# DAC_channel.net
KiCad netlist of a schematic drawn in Altium Designer
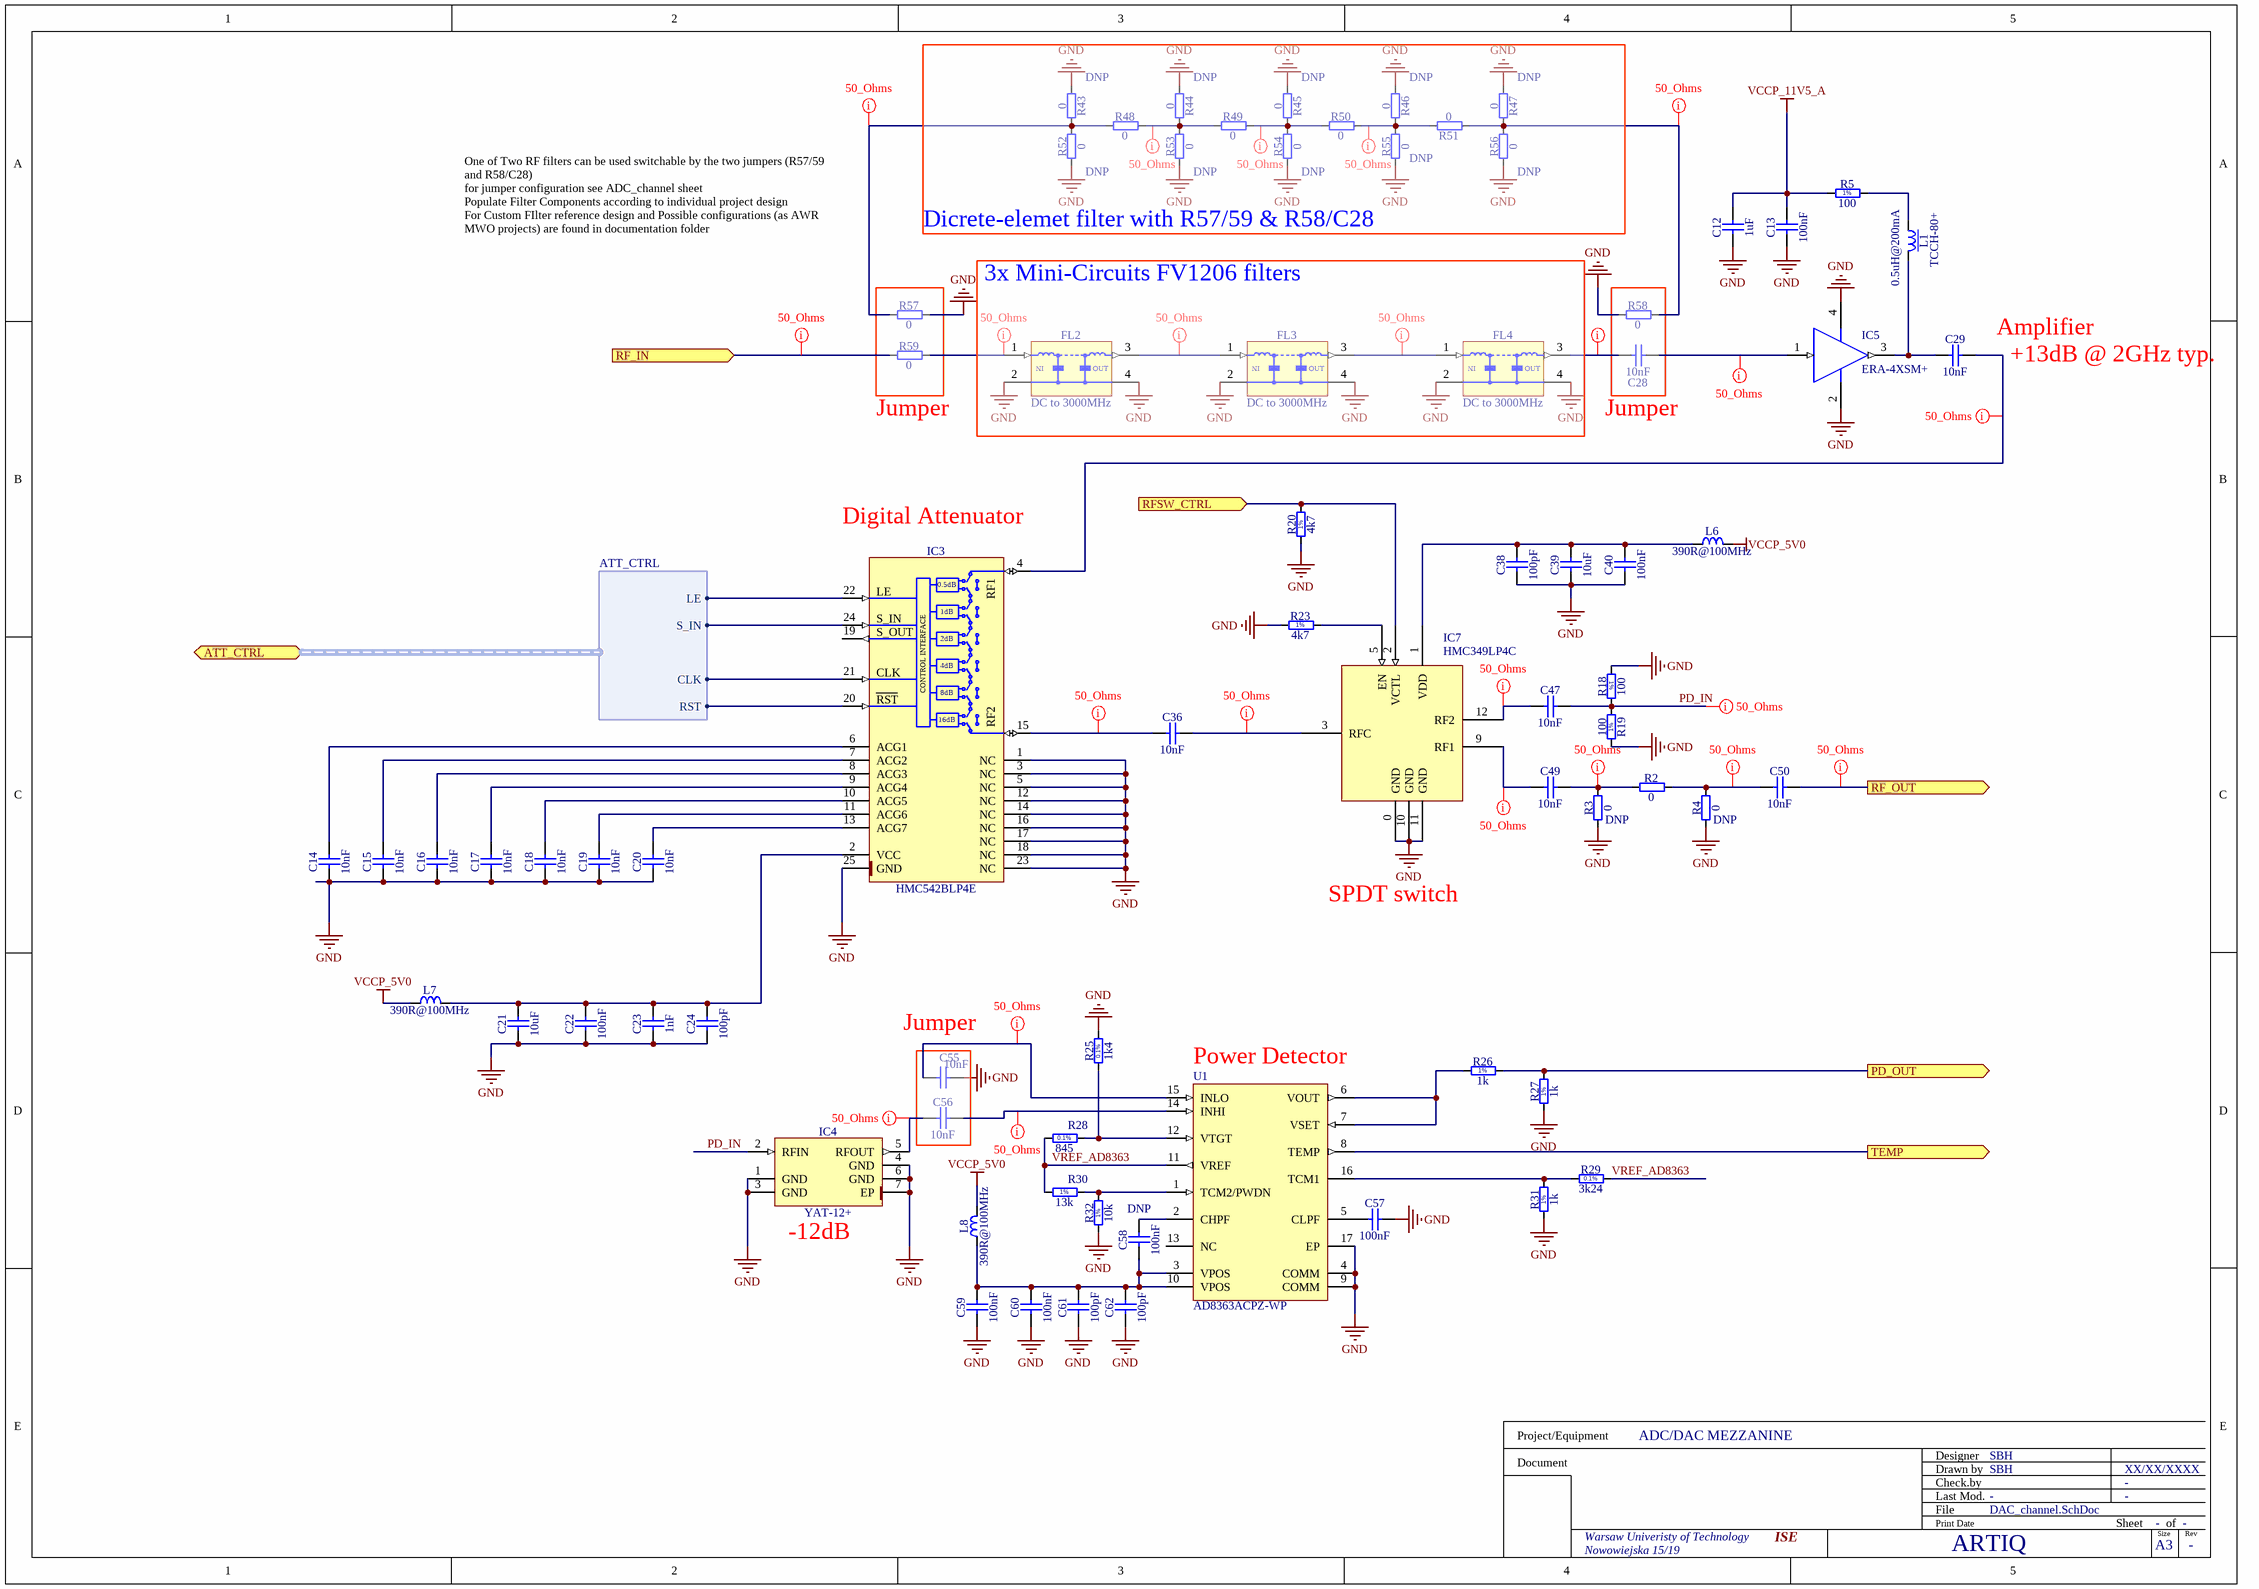
[diagram p0: DAC_channel.SchDoc]

(export (version "E")
  (design (tool "Eeschema 10.0.6"))
  (components
    (comp (ref "C12")
      (value "1uF")
      (footprint "CAPC2012X140N")
      (description "Non-polarised capacitor")
      (fields
        (field (name "PART NUMBER") "CC0805_1UF_35V_20%_X7R")
        (field (name "VOLTAGE") "35V")
        (field (name "AUTHOR") "CERN DEM JLC")
      )
      (libsource (lib "Capacitors") (part "Capacitor - non polarized"))
    )
    (comp (ref "C13")
      (value "100nF")
      (footprint "CAPC1608X87N")
      (description "Non-polarised capacitor")
      (fields
        (field (name "PART NUMBER") "CC0603_100NF_50V_10%_X7R")
        (field (name "VOLTAGE") "50V")
        (field (name "AUTHOR") "CERN DEM JLC")
      )
      (libsource (lib "Capacitors") (part "Capacitor - non polarized"))
    )
    (comp (ref "C14")
      (value "10nF")
      (footprint "CAPC1005X55N")
      (description "Non-polarised capacitor")
      (fields
        (field (name "PART NUMBER") "CC0402_10NF_16V_10%_X7R")
        (field (name "VOLTAGE") "16V")
        (field (name "AUTHOR") "CERN DEM JLC")
      )
      (libsource (lib "Capacitors") (part "Capacitor - non polarized"))
    )
    (comp (ref "C15")
      (value "10nF")
      (footprint "CAPC1005X55N")
      (description "Non-polarised capacitor")
      (fields
        (field (name "PART NUMBER") "CC0402_10NF_16V_10%_X7R")
        (field (name "VOLTAGE") "16V")
        (field (name "AUTHOR") "CERN DEM JLC")
      )
      (libsource (lib "Capacitors") (part "Capacitor - non polarized"))
    )
    (comp (ref "C16")
      (value "10nF")
      (footprint "CAPC1005X55N")
      (description "Non-polarised capacitor")
      (fields
        (field (name "PART NUMBER") "CC0402_10NF_16V_10%_X7R")
        (field (name "VOLTAGE") "16V")
        (field (name "AUTHOR") "CERN DEM JLC")
      )
      (libsource (lib "Capacitors") (part "Capacitor - non polarized"))
    )
    (comp (ref "C17")
      (value "10nF")
      (footprint "CAPC1005X55N")
      (description "Non-polarised capacitor")
      (fields
        (field (name "PART NUMBER") "CC0402_10NF_16V_10%_X7R")
        (field (name "VOLTAGE") "16V")
        (field (name "AUTHOR") "CERN DEM JLC")
      )
      (libsource (lib "Capacitors") (part "Capacitor - non polarized"))
    )
    (comp (ref "C18")
      (value "10nF")
      (footprint "CAPC1005X55N")
      (description "Non-polarised capacitor")
      (fields
        (field (name "PART NUMBER") "CC0402_10NF_16V_10%_X7R")
        (field (name "VOLTAGE") "16V")
        (field (name "AUTHOR") "CERN DEM JLC")
      )
      (libsource (lib "Capacitors") (part "Capacitor - non polarized"))
    )
    (comp (ref "C19")
      (value "10nF")
      (footprint "CAPC1005X55N")
      (description "Non-polarised capacitor")
      (fields
        (field (name "PART NUMBER") "CC0402_10NF_16V_10%_X7R")
        (field (name "VOLTAGE") "16V")
        (field (name "AUTHOR") "CERN DEM JLC")
      )
      (libsource (lib "Capacitors") (part "Capacitor - non polarized"))
    )
    (comp (ref "C20")
      (value "10nF")
      (footprint "CAPC1005X55N")
      (description "Non-polarised capacitor")
      (fields
        (field (name "PART NUMBER") "CC0402_10NF_16V_10%_X7R")
        (field (name "VOLTAGE") "16V")
        (field (name "AUTHOR") "CERN DEM JLC")
      )
      (libsource (lib "Capacitors") (part "Capacitor - non polarized"))
    )
    (comp (ref "C21")
      (value "10uF")
      (footprint "CAPC1608X80N")
      (description "Non-polarised capacitor")
      (fields
        (field (name "PART NUMBER") "CC0603_10UF_16V_20%_X5R")
        (field (name "VOLTAGE") "16V")
        (field (name "AUTHOR") "CERN DEM MR")
      )
      (libsource (lib "Capacitors") (part "Capacitor - non polarized"))
    )
    (comp (ref "C22")
      (value "100nF")
      (footprint "CAPC1005X55N")
      (description "Non-polarised capacitor")
      (fields
        (field (name "PART NUMBER") "CC0402_100NF_16V_10%_X7R")
        (field (name "VOLTAGE") "16V")
        (field (name "AUTHOR") "CERN DEM JLC")
      )
      (libsource (lib "Capacitors") (part "Capacitor - non polarized"))
    )
    (comp (ref "C23")
      (value "1nF")
      (footprint "CAPC1005X55N")
      (description "Non-polarised capacitor")
      (fields
        (field (name "PART NUMBER") "CC0402_1NF_50V_10%_X7R")
        (field (name "VOLTAGE") "50V")
        (field (name "AUTHOR") "CERN DEM JLC")
      )
      (libsource (lib "Capacitors") (part "Capacitor - non polarized"))
    )
    (comp (ref "C24")
      (value "100pF")
      (footprint "CAPC1005X55N")
      (description "Non-polarised capacitor")
      (fields
        (field (name "PART NUMBER") "CC0402_100PF_50V_5%_C0G")
        (field (name "VOLTAGE") "50V")
        (field (name "AUTHOR") "CERN DEM JLC")
      )
      (libsource (lib "Capacitors") (part "Capacitor - non polarized"))
    )
    (comp (ref "C28")
      (value "10nF")
      (footprint "CAPC1005X55N")
      (description "Non-polarised capacitor")
      (fields
        (field (name "PART NUMBER") "CC0402_10NF_16V_10%_X7R")
        (field (name "VOLTAGE") "16V")
        (field (name "AUTHOR") "CERN DEM JLC")
      )
      (libsource (lib "Capacitors") (part "Capacitor - non polarized"))
    )
    (comp (ref "C29")
      (value "10nF")
      (footprint "CAPC1005X55N")
      (description "Non-polarised capacitor")
      (fields
        (field (name "PART NUMBER") "CC0402_10NF_16V_10%_X7R")
        (field (name "VOLTAGE") "16V")
        (field (name "AUTHOR") "CERN DEM JLC")
      )
      (libsource (lib "Capacitors") (part "Capacitor - non polarized"))
    )
    (comp (ref "C36")
      (value "10nF")
      (footprint "CAPC1005X55N")
      (description "Non-polarised capacitor")
      (fields
        (field (name "PART NUMBER") "CC0402_10NF_16V_10%_X7R")
        (field (name "VOLTAGE") "16V")
        (field (name "AUTHOR") "CERN DEM JLC")
      )
      (libsource (lib "Capacitors") (part "Capacitor - non polarized"))
    )
    (comp (ref "C38")
      (value "100pF")
      (footprint "CAPC1005X55N")
      (description "Non-polarised capacitor")
      (fields
        (field (name "PART NUMBER") "CC0402_100PF_50V_5%_C0G")
        (field (name "VOLTAGE") "50V")
        (field (name "AUTHOR") "CERN DEM JLC")
      )
      (libsource (lib "Capacitors") (part "Capacitor - non polarized"))
    )
    (comp (ref "C39")
      (value "10uF")
      (footprint "CAPC1608X80N")
      (description "Non-polarised capacitor")
      (fields
        (field (name "PART NUMBER") "CC0603_10UF_16V_20%_X5R")
        (field (name "VOLTAGE") "16V")
        (field (name "AUTHOR") "CERN DEM MR")
      )
      (libsource (lib "Capacitors") (part "Capacitor - non polarized"))
    )
    (comp (ref "C40")
      (value "100nF")
      (footprint "CAPC1005X55N")
      (description "Non-polarised capacitor")
      (fields
        (field (name "PART NUMBER") "CC0402_100NF_16V_10%_X7R")
        (field (name "VOLTAGE") "16V")
        (field (name "AUTHOR") "CERN DEM JLC")
      )
      (libsource (lib "Capacitors") (part "Capacitor - non polarized"))
    )
    (comp (ref "C47")
      (value "10nF")
      (footprint "CAPC1005X55N")
      (description "Non-polarised capacitor")
      (fields
        (field (name "PART NUMBER") "CC0402_10NF_16V_10%_X7R")
        (field (name "VOLTAGE") "16V")
        (field (name "AUTHOR") "CERN DEM JLC")
      )
      (libsource (lib "Capacitors") (part "Capacitor - non polarized"))
    )
    (comp (ref "C49")
      (value "10nF")
      (footprint "CAPC1005X55N")
      (description "Non-polarised capacitor")
      (fields
        (field (name "PART NUMBER") "CC0402_10NF_16V_10%_X7R")
        (field (name "VOLTAGE") "16V")
        (field (name "AUTHOR") "CERN DEM JLC")
      )
      (libsource (lib "Capacitors") (part "Capacitor - non polarized"))
    )
    (comp (ref "C50")
      (value "10nF")
      (footprint "CAPC1005X55N")
      (description "Non-polarised capacitor")
      (fields
        (field (name "PART NUMBER") "CC0402_10NF_16V_10%_X7R")
        (field (name "VOLTAGE") "16V")
        (field (name "AUTHOR") "CERN DEM JLC")
      )
      (libsource (lib "Capacitors") (part "Capacitor - non polarized"))
    )
    (comp (ref "C55")
      (value "10nF")
      (footprint "CAPC1005X55N")
      (description "Non-polarised capacitor")
      (fields
        (field (name "PART NUMBER") "CC0402_10NF_16V_10%_X7R")
        (field (name "VOLTAGE") "16V")
        (field (name "AUTHOR") "CERN DEM JLC")
      )
      (libsource (lib "Capacitors") (part "Capacitor - non polarized"))
    )
    (comp (ref "C56")
      (value "10nF")
      (footprint "CAPC1005X55N")
      (description "Non-polarised capacitor")
      (fields
        (field (name "PART NUMBER") "CC0402_10NF_16V_10%_X7R")
        (field (name "VOLTAGE") "16V")
        (field (name "AUTHOR") "CERN DEM JLC")
      )
      (libsource (lib "Capacitors") (part "Capacitor - non polarized"))
    )
    (comp (ref "C57")
      (value "100nF")
      (footprint "CAPC1005X55N")
      (description "Non-polarised capacitor")
      (fields
        (field (name "PART NUMBER") "CC0402_100NF_16V_10%_X5R")
        (field (name "VOLTAGE") "16V")
        (field (name "AUTHOR") "CERN DEM JLC")
      )
      (libsource (lib "Capacitors") (part "Capacitor - non polarized"))
    )
    (comp (ref "C58")
      (value "100nF")
      (footprint "CAPC1005X55N")
      (description "Non-polarised capacitor")
      (fields
        (field (name "PART NUMBER") "CC0402_100NF_16V_10%_X5R")
        (field (name "VOLTAGE") "16V")
        (field (name "MOUNTED") "DNP")
        (field (name "AUTHOR") "CERN DEM JLC")
      )
      (libsource (lib "Capacitors") (part "Capacitor - non polarized"))
    )
    (comp (ref "C59")
      (value "100nF")
      (footprint "CAPC1005X55N")
      (description "Non-polarised capacitor")
      (fields
        (field (name "PART NUMBER") "CC0402_100NF_16V_10%_X5R")
        (field (name "VOLTAGE") "16V")
        (field (name "AUTHOR") "CERN DEM JLC")
      )
      (libsource (lib "Capacitors") (part "Capacitor - non polarized"))
    )
    (comp (ref "C60")
      (value "100nF")
      (footprint "CAPC1005X55N")
      (description "Non-polarised capacitor")
      (fields
        (field (name "PART NUMBER") "CC0402_100NF_16V_10%_X5R")
        (field (name "VOLTAGE") "16V")
        (field (name "AUTHOR") "CERN DEM JLC")
      )
      (libsource (lib "Capacitors") (part "Capacitor - non polarized"))
    )
    (comp (ref "C61")
      (value "100pF")
      (footprint "CAPC1005X55N")
      (description "Non-polarised capacitor")
      (fields
        (field (name "PART NUMBER") "CC0402_100PF_50V_5%_C0G")
        (field (name "VOLTAGE") "50V")
        (field (name "AUTHOR") "CERN DEM JLC")
      )
      (libsource (lib "Capacitors") (part "Capacitor - non polarized"))
    )
    (comp (ref "C62")
      (value "100pF")
      (footprint "CAPC1005X55N")
      (description "Non-polarised capacitor")
      (fields
        (field (name "PART NUMBER") "CC0402_100PF_50V_5%_C0G")
        (field (name "VOLTAGE") "50V")
        (field (name "AUTHOR") "CERN DEM JLC")
      )
      (libsource (lib "Capacitors") (part "Capacitor - non polarized"))
    )
    (comp (ref "FL2")
      (value "DC to 3000MHz")
      (footprint "FIL_MINI-CIRCUITS_FV1206")
      (description "50 Ohm DC to 3000MHz Low Pass Filter")
      (fields
        (field (name "PART NUMBER") "FIL_MINI-CIRCUITS_LFCN-3000+")
        (field (name "MANUFACTURER") "MINI-CIRCUITS")
        (field (name "AUTHOR") "CERN DEM JLC")
      )
      (libsource (lib "Inductors & Transformers") (part "FIL_MINI-CIRCUITS_LFCN-3000+"))
    )
    (comp (ref "FL3")
      (value "DC to 3000MHz")
      (footprint "FIL_MINI-CIRCUITS_FV1206")
      (description "50 Ohm DC to 3000MHz Low Pass Filter")
      (fields
        (field (name "PART NUMBER") "FIL_MINI-CIRCUITS_LFCN-3000+")
        (field (name "MANUFACTURER") "MINI-CIRCUITS")
        (field (name "AUTHOR") "CERN DEM JLC")
      )
      (libsource (lib "Inductors & Transformers") (part "FIL_MINI-CIRCUITS_LFCN-3000+"))
    )
    (comp (ref "FL4")
      (value "DC to 3000MHz")
      (footprint "FIL_MINI-CIRCUITS_FV1206")
      (description "50 Ohm DC to 3000MHz Low Pass Filter")
      (fields
        (field (name "PART NUMBER") "FIL_MINI-CIRCUITS_LFCN-3000+")
        (field (name "MANUFACTURER") "MINI-CIRCUITS")
        (field (name "AUTHOR") "CERN DEM JLC")
      )
      (libsource (lib "Inductors & Transformers") (part "FIL_MINI-CIRCUITS_LFCN-3000+"))
    )
    (comp (ref "IC3")
      (value "HMC542BLP4E")
      (footprint "QFN50P400X400X100-25N-S295")
      (description "0.5dB LSB GaAs MMIC 6-bit Digital Serial Control Attenuator, DC - 4GHz")
      (fields (field (name "MANUFACTURER") "HITTITE MICROWAVE CORP") (field (name "AUTHOR") "CERN DEM JMW"))
      (libsource (lib "ICs And Semiconductors") (part "HMC542BLP4E"))
    )
    (comp (ref "IC4")
      (value "YAT-12+")
      (footprint "MINI-CIRCUITS_MC1630")
      (description "DC to 18GHz, 2W, 50 Ohm, 4dB Attenuator")
      (fields (field (name "MANUFACTURER") "MINI-CIRCUITS") (field (name "AUTHOR") "CERN DEM JLC"))
      (libsource (lib "ICs And Semiconductors") (part "YAT-XX+"))
    )
    (comp (ref "IC5")
      (value "ERA-4XSM+")
      (footprint "MINI-CIRCUITS_WW107")
      (description "DC-4GHz Monolithic Amplifier")
      (fields (field (name "MANUFACTURER") "MINI-CIRCUITS") (field (name "AUTHOR") "CERN DEM JMW"))
      (libsource (lib "ICs And Semiconductors") (part "ERA-4XSM+"))
    )
    (comp (ref "IC7")
      (value "HMC349LP4C")
      (footprint "uRFB_CLKIN3:QFN65P400X400X100-16N")
      (description "Hittite RF Switch, SPDT, Non-Reflective")
      (libsource (lib "uRFB_CLKIN3") (part "HMC349LP4C"))
    )
    (comp (ref "L1")
      (value "0.5uH@200mA")
      (footprint "IND_MINI-CIRCUITS_GU1604")
      (description "50 Ohms, 50 to 8200 MHz RF Choke")
      (fields
        (field (name "PART NUMBER") "IND_MINI-CIRCUITS_TCCH-80+")
        (field (name "POWER") "200mA")
        (field (name "MANUFACTURER PART NUMBER") "TCCH-80+")
        (field (name "AUTHOR") "CERN DEM JLC")
      )
      (libsource (lib "Inductors & Transformers") (part "IND_MINI-CIRCUITS_TCCH-80+"))
    )
    (comp (ref "L6")
      (value "390R@100MHz")
      (footprint "INDC1608X95N")
      (description "Inductor")
      (fields
        (field (name "PART NUMBER") "IND0603_TDK_MPZ1608R391A")
        (field (name "POWER") "1.2A")
        (field (name "AUTHOR") "CERN DEM JLC")
      )
      (libsource (lib "Inductors & Transformers") (part "Inductor"))
    )
    (comp (ref "L7")
      (value "390R@100MHz")
      (footprint "INDC1608X95N")
      (description "Inductor")
      (fields
        (field (name "PART NUMBER") "IND0603_TDK_MPZ1608R391A")
        (field (name "POWER") "1.2A")
        (field (name "AUTHOR") "CERN DEM JLC")
      )
      (libsource (lib "Inductors & Transformers") (part "Inductor"))
    )
    (comp (ref "L8")
      (value "390R@100MHz")
      (footprint "INDC1608X95N")
      (description "Inductor")
      (fields
        (field (name "PART NUMBER") "IND0603_TDK_MPZ1608R391A")
        (field (name "POWER") "1.2A")
        (field (name "AUTHOR") "CERN DEM JLC")
      )
      (libsource (lib "") (part "Inductor_1"))
    )
    (comp (ref "R2")
      (value "0")
      (footprint "RESC1005X40N")
      (description "Resistor")
      (fields
        (field (name "PART NUMBER") "R0402_0R_JUMPER")
        (field (name "MANUFACTURER") "GENERIC")
        (field (name "AUTHOR") "CERN DEM JLC")
      )
      (libsource (lib "Resistors") (part "Resistor"))
    )
    (comp (ref "R3")
      (value "0")
      (footprint "RESC1005X40N")
      (description "Resistor")
      (fields
        (field (name "PART NUMBER") "R0402_0R_JUMPER")
        (field (name "MANUFACTURER") "GENERIC")
        (field (name "MOUNTED") "DNP")
        (field (name "AUTHOR") "CERN DEM JLC")
      )
      (libsource (lib "Resistors") (part "Resistor"))
    )
    (comp (ref "R4")
      (value "0")
      (footprint "RESC1005X40N")
      (description "Resistor")
      (fields
        (field (name "PART NUMBER") "R0402_0R_JUMPER")
        (field (name "MANUFACTURER") "GENERIC")
        (field (name "MOUNTED") "DNP")
        (field (name "AUTHOR") "CERN DEM JLC")
      )
      (libsource (lib "Resistors") (part "Resistor"))
    )
    (comp (ref "R5")
      (value "100")
      (footprint "RESC3216X65N")
      (description "Resistor - 1%")
      (fields
        (field (name "PART NUMBER") "R1206_100R_1%_0.25W_100PPM")
        (field (name "POWER") "0.25W")
        (field (name "AUTHOR") "CERN DEM JLC")
      )
      (libsource (lib "Resistors") (part "Resistor - 1%"))
    )
    (comp (ref "R18")
      (value "100")
      (footprint "RESC0603X28N")
      (description "Resistor - 1%")
      (fields
        (field (name "PART NUMBER") "R0201_100R_1%_0.05W_200PPM")
        (field (name "POWER") "0.05W")
        (field (name "AUTHOR") "CERN DEM JLC")
      )
      (libsource (lib "Resistors") (part "Resistor - 1%"))
    )
    (comp (ref "R19")
      (value "100")
      (footprint "RESC0603X28N")
      (description "Resistor - 1%")
      (fields
        (field (name "PART NUMBER") "R0201_100R_1%_0.05W_200PPM")
        (field (name "POWER") "0.05W")
        (field (name "AUTHOR") "CERN DEM JLC")
      )
      (libsource (lib "Resistors") (part "Resistor - 1%"))
    )
    (comp (ref "R20")
      (value "4k7")
      (footprint "RESC1005X40N")
      (description "Resistor - 1%")
      (fields
        (field (name "PART NUMBER") "R0402_4K7_1%_0.0625W_100PPM")
        (field (name "POWER") "0.0625W")
        (field (name "AUTHOR") "CERN DEM JLC")
      )
      (libsource (lib "Resistors") (part "Resistor - 1%"))
    )
    (comp (ref "R23")
      (value "4k7")
      (footprint "RESC1005X40N")
      (description "Resistor - 1%")
      (fields
        (field (name "PART NUMBER") "R0402_4K7_1%_0.0625W_100PPM")
        (field (name "POWER") "0.0625W")
        (field (name "AUTHOR") "CERN DEM JLC")
      )
      (libsource (lib "Resistors") (part "Resistor - 1%"))
    )
    (comp (ref "R25")
      (value "1k4")
      (footprint "RESC1608X55N")
      (description "Resistor - 0.1%")
      (fields
        (field (name "PART NUMBER") "R0603_1K4_0.1%_0.063W_10PPM")
        (field (name "POWER") "0.063W")
        (field (name "AUTHOR") "CERN DEM JLC")
      )
      (libsource (lib "Resistors") (part "Resistor - 0.1%"))
    )
    (comp (ref "R26")
      (value "1k")
      (footprint "RESC1005X40N")
      (description "Resistor - 1%")
      (fields
        (field (name "PART NUMBER") "R0402_1K_1%_0.0625W_100PPM")
        (field (name "POWER") "0.0625W")
        (field (name "AUTHOR") "CERN DEM JLC")
      )
      (libsource (lib "Resistors") (part "Resistor - 1%"))
    )
    (comp (ref "R27")
      (value "1k")
      (footprint "RESC1005X40N")
      (description "Resistor - 1%")
      (fields
        (field (name "PART NUMBER") "R0402_1K_1%_0.0625W_100PPM")
        (field (name "POWER") "0.0625W")
        (field (name "AUTHOR") "CERN DEM JLC")
      )
      (libsource (lib "Resistors") (part "Resistor - 1%"))
    )
    (comp (ref "R28")
      (value "845")
      (footprint "RESC1608X55N")
      (description "Resistor - 0.1%")
      (fields
        (field (name "PART NUMBER") "R0603_845R_0.1%_0.063W_10PPM")
        (field (name "POWER") "0.063W")
        (field (name "AUTHOR") "CERN DEM JLC")
      )
      (libsource (lib "Resistors") (part "Resistor - 0.1%"))
    )
    (comp (ref "R29")
      (value "3k24")
      (footprint "RESC1608X55N")
      (description "Resistor - 0.1%")
      (fields
        (field (name "PART NUMBER") "R0603_3K24_0.1%_0.063W_10PPM")
        (field (name "POWER") "0.063W")
        (field (name "AUTHOR") "CERN DEM JLC")
      )
      (libsource (lib "Resistors") (part "Resistor - 0.1%"))
    )
    (comp (ref "R30")
      (value "13k")
      (footprint "RESC1005X40N")
      (description "Resistor - 1%")
      (fields
        (field (name "PART NUMBER") "R0402_13K_1%_0.0625W_100PPM")
        (field (name "POWER") "0.0625W")
        (field (name "AUTHOR") "CERN DEM JLC")
      )
      (libsource (lib "Resistors") (part "Resistor - 1%"))
    )
    (comp (ref "R31")
      (value "1k")
      (footprint "RESC1005X40N")
      (description "Resistor - 1%")
      (fields
        (field (name "PART NUMBER") "R0402_1K_1%_0.0625W_100PPM")
        (field (name "POWER") "0.0625W")
        (field (name "AUTHOR") "CERN DEM JLC")
      )
      (libsource (lib "Resistors") (part "Resistor - 1%"))
    )
    (comp (ref "R32")
      (value "10k")
      (footprint "RESC1005X40N")
      (description "Resistor - 1%")
      (fields
        (field (name "PART NUMBER") "R0402_10K_1%_0.0625W_100PPM")
        (field (name "POWER") "0.0625W")
        (field (name "AUTHOR") "CERN DEM JLC")
      )
      (libsource (lib "Resistors") (part "Resistor - 1%"))
    )
    (comp (ref "R43")
      (value "0")
      (footprint "RESC1005X40N")
      (description "Resistor")
      (fields
        (field (name "PART NUMBER") "R0402_0R_JUMPER")
        (field (name "MANUFACTURER") "GENERIC")
        (field (name "MOUNTED") "DNP")
        (field (name "AUTHOR") "CERN DEM JLC")
      )
      (libsource (lib "Resistors") (part "Resistor"))
    )
    (comp (ref "R44")
      (value "0")
      (footprint "RESC1005X40N")
      (description "Resistor")
      (fields
        (field (name "PART NUMBER") "R0402_0R_JUMPER")
        (field (name "MANUFACTURER") "GENERIC")
        (field (name "MOUNTED") "DNP")
        (field (name "AUTHOR") "CERN DEM JLC")
      )
      (libsource (lib "Resistors") (part "Resistor"))
    )
    (comp (ref "R45")
      (value "0")
      (footprint "RESC1005X40N")
      (description "Resistor")
      (fields
        (field (name "PART NUMBER") "R0402_0R_JUMPER")
        (field (name "MANUFACTURER") "GENERIC")
        (field (name "MOUNTED") "DNP")
        (field (name "AUTHOR") "CERN DEM JLC")
      )
      (libsource (lib "Resistors") (part "Resistor"))
    )
    (comp (ref "R46")
      (value "0")
      (footprint "RESC1005X40N")
      (description "Resistor")
      (fields
        (field (name "PART NUMBER") "R0402_0R_JUMPER")
        (field (name "MANUFACTURER") "GENERIC")
        (field (name "MOUNTED") "DNP")
        (field (name "AUTHOR") "CERN DEM JLC")
      )
      (libsource (lib "Resistors") (part "Resistor"))
    )
    (comp (ref "R47")
      (value "0")
      (footprint "RESC1005X40N")
      (description "Resistor")
      (fields
        (field (name "PART NUMBER") "R0402_0R_JUMPER")
        (field (name "MANUFACTURER") "GENERIC")
        (field (name "MOUNTED") "DNP")
        (field (name "AUTHOR") "CERN DEM JLC")
      )
      (libsource (lib "Resistors") (part "Resistor"))
    )
    (comp (ref "R48")
      (value "0")
      (footprint "RESC1005X40N")
      (description "Resistor")
      (fields
        (field (name "PART NUMBER") "R0402_0R_JUMPER")
        (field (name "MANUFACTURER") "GENERIC")
        (field (name "AUTHOR") "CERN DEM JLC")
      )
      (libsource (lib "Resistors") (part "Resistor"))
    )
    (comp (ref "R49")
      (value "0")
      (footprint "RESC1005X40N")
      (description "Resistor")
      (fields
        (field (name "PART NUMBER") "R0402_0R_JUMPER")
        (field (name "MANUFACTURER") "GENERIC")
        (field (name "AUTHOR") "CERN DEM JLC")
      )
      (libsource (lib "Resistors") (part "Resistor"))
    )
    (comp (ref "R50")
      (value "0")
      (footprint "RESC1005X40N")
      (description "Resistor")
      (fields
        (field (name "PART NUMBER") "R0402_0R_JUMPER")
        (field (name "MANUFACTURER") "GENERIC")
        (field (name "AUTHOR") "CERN DEM JLC")
      )
      (libsource (lib "Resistors") (part "Resistor"))
    )
    (comp (ref "R51")
      (value "0")
      (footprint "RESC1005X40N")
      (description "Resistor")
      (fields
        (field (name "PART NUMBER") "R0402_0R_JUMPER")
        (field (name "MANUFACTURER") "GENERIC")
        (field (name "AUTHOR") "CERN DEM JLC")
      )
      (libsource (lib "Resistors") (part "Resistor"))
    )
    (comp (ref "R52")
      (value "0")
      (footprint "RESC1005X40N")
      (description "Resistor")
      (fields
        (field (name "PART NUMBER") "R0402_0R_JUMPER")
        (field (name "MANUFACTURER") "GENERIC")
        (field (name "MOUNTED") "DNP")
        (field (name "AUTHOR") "CERN DEM JLC")
      )
      (libsource (lib "Resistors") (part "Resistor"))
    )
    (comp (ref "R53")
      (value "0")
      (footprint "RESC1005X40N")
      (description "Resistor")
      (fields
        (field (name "PART NUMBER") "R0402_0R_JUMPER")
        (field (name "MANUFACTURER") "GENERIC")
        (field (name "MOUNTED") "DNP")
        (field (name "AUTHOR") "CERN DEM JLC")
      )
      (libsource (lib "Resistors") (part "Resistor"))
    )
    (comp (ref "R54")
      (value "0")
      (footprint "RESC1005X40N")
      (description "Resistor")
      (fields
        (field (name "PART NUMBER") "R0402_0R_JUMPER")
        (field (name "MANUFACTURER") "GENERIC")
        (field (name "MOUNTED") "DNP")
        (field (name "AUTHOR") "CERN DEM JLC")
      )
      (libsource (lib "Resistors") (part "Resistor"))
    )
    (comp (ref "R55")
      (value "0")
      (footprint "RESC1005X40N")
      (description "Resistor")
      (fields
        (field (name "PART NUMBER") "R0402_0R_JUMPER")
        (field (name "MANUFACTURER") "GENERIC")
        (field (name "MOUNTED") "DNP")
        (field (name "AUTHOR") "CERN DEM JLC")
      )
      (libsource (lib "Resistors") (part "Resistor"))
    )
    (comp (ref "R56")
      (value "0")
      (footprint "RESC1005X40N")
      (description "Resistor")
      (fields
        (field (name "PART NUMBER") "R0402_0R_JUMPER")
        (field (name "MANUFACTURER") "GENERIC")
        (field (name "MOUNTED") "DNP")
        (field (name "AUTHOR") "CERN DEM JLC")
      )
      (libsource (lib "Resistors") (part "Resistor"))
    )
    (comp (ref "R57")
      (value "0")
      (footprint "RESC1005X40N")
      (description "Resistor")
      (fields
        (field (name "PART NUMBER") "R0402_0R_JUMPER")
        (field (name "MANUFACTURER") "GENERIC")
        (field (name "AUTHOR") "CERN DEM JLC")
      )
      (libsource (lib "Resistors") (part "Resistor"))
    )
    (comp (ref "R58")
      (value "0")
      (footprint "RESC1005X40N")
      (description "Resistor")
      (fields
        (field (name "PART NUMBER") "R0402_0R_JUMPER")
        (field (name "MANUFACTURER") "GENERIC")
        (field (name "AUTHOR") "CERN DEM JLC")
      )
      (libsource (lib "Resistors") (part "Resistor"))
    )
    (comp (ref "R59")
      (value "0")
      (footprint "RESC1005X40N")
      (description "Resistor")
      (fields
        (field (name "PART NUMBER") "R0402_0R_JUMPER")
        (field (name "MANUFACTURER") "GENERIC")
        (field (name "AUTHOR") "CERN DEM JLC")
      )
      (libsource (lib "Resistors") (part "Resistor"))
    )
    (comp (ref "U1")
      (value "AD8363ACPZ-WP")
      (footprint "ADI-CP-16-10_M")
      (description "50 Hz to 6 GHz,50 dB TruPwr™ Detector, 3µs Response Time, CP-16-10, Pb-Free, 64 Tray")
      (libsource (lib "Altium Content Vault") (part "ADI-AD8363-CP-16-10"))
    )
  )
  (nets
    (net (code "2") (name "/CLK") (class "Default")
      (node (ref "IC3") (pin "21") (pinfunction "SHIFT_CLOCK_21") (pintype "input"))
    )
    (net (code "3") (name "/LE") (class "Default")
      (node (ref "IC3") (pin "22") (pinfunction "LATCH_ENABLE_22") (pintype "input"))
    )
    (net (code "4") (name "/PD_IN") (class "Default")
      (node (ref "C47") (pin "2") (pinfunction "2_2") (pintype "passive"))
      (node (ref "IC4") (pin "2") (pinfunction "RFIN_2") (pintype "input"))
      (node (ref "R18") (pin "2") (pinfunction "2_2") (pintype "passive"))
      (node (ref "R19") (pin "2") (pinfunction "2_2") (pintype "passive"))
    )
    (net (code "5") (name "/PD_OUT") (class "Default")
      (node (ref "R26") (pin "2") (pinfunction "2_2") (pintype "passive"))
      (node (ref "R27") (pin "2") (pinfunction "2_2") (pintype "passive"))
    )
    (net (code "6") (name "/RFSW_CTRL") (class "Default")
      (node (ref "IC7") (pin "2") (pinfunction "VCTL_2") (pintype "input"))
      (node (ref "R20") (pin "2") (pinfunction "2_2") (pintype "passive"))
    )
    (net (code "7") (name "/RF_IN") (class "Default")
      (node (ref "R59") (pin "1") (pinfunction "1_1") (pintype "passive"))
    )
    (net (code "8") (name "/RF_OUT") (class "Default")
      (node (ref "C50") (pin "2") (pinfunction "2_2") (pintype "passive"))
    )
    (net (code "9") (name "/RST") (class "Default")
      (node (ref "IC3") (pin "20") (pinfunction "~{RESET}_20") (pintype "input"))
    )
    (net (code "10") (name "/S_IN") (class "Default")
      (node (ref "IC3") (pin "24") (pinfunction "SERIAL_INPUT_24") (pintype "input"))
    )
    (net (code "11") (name "/TEMP") (class "Default")
      (node (ref "U1") (pin "8") (pinfunction "TEMP_8") (pintype "output"))
    )
    (net (code "12") (name "/VREF_AD8363") (class "Default")
      (node (ref "R28") (pin "1") (pinfunction "1_1") (pintype "passive"))
      (node (ref "R29") (pin "2") (pinfunction "2_2") (pintype "passive"))
      (node (ref "R30") (pin "1") (pinfunction "1_1") (pintype "passive"))
      (node (ref "U1") (pin "11") (pinfunction "VREF_11") (pintype "output"))
    )
    (net (code "14") (name "GND") (class "Default")
      (node (ref "C12") (pin "1") (pinfunction "1_1") (pintype "passive"))
      (node (ref "C13") (pin "1") (pinfunction "1_1") (pintype "passive"))
      (node (ref "C14") (pin "1") (pinfunction "1_1") (pintype "passive"))
      (node (ref "C15") (pin "1") (pinfunction "1_1") (pintype "passive"))
      (node (ref "C16") (pin "1") (pinfunction "1_1") (pintype "passive"))
      (node (ref "C17") (pin "1") (pinfunction "1_1") (pintype "passive"))
      (node (ref "C18") (pin "1") (pinfunction "1_1") (pintype "passive"))
      (node (ref "C19") (pin "1") (pinfunction "1_1") (pintype "passive"))
      (node (ref "C20") (pin "1") (pinfunction "1_1") (pintype "passive"))
      (node (ref "C21") (pin "1") (pinfunction "1_1") (pintype "passive"))
      (node (ref "C22") (pin "1") (pinfunction "1_1") (pintype "passive"))
      (node (ref "C23") (pin "1") (pinfunction "1_1") (pintype "passive"))
      (node (ref "C24") (pin "1") (pinfunction "1_1") (pintype "passive"))
      (node (ref "C38") (pin "2") (pinfunction "2_2") (pintype "passive"))
      (node (ref "C39") (pin "1") (pinfunction "1_1") (pintype "passive"))
      (node (ref "C40") (pin "1") (pinfunction "1_1") (pintype "passive"))
      (node (ref "C55") (pin "1") (pinfunction "1_1") (pintype "passive"))
      (node (ref "C57") (pin "2") (pinfunction "2_2") (pintype "passive"))
      (node (ref "C59") (pin "1") (pinfunction "1_1") (pintype "passive"))
      (node (ref "C60") (pin "1") (pinfunction "1_1") (pintype "passive"))
      (node (ref "C61") (pin "2") (pinfunction "2_2") (pintype "passive"))
      (node (ref "C62") (pin "2") (pinfunction "2_2") (pintype "passive"))
      (node (ref "FL2") (pin "2") (pinfunction "GND_2") (pintype "power_in"))
      (node (ref "FL2") (pin "4") (pinfunction "GND_4") (pintype "power_in"))
      (node (ref "FL3") (pin "2") (pinfunction "GND_2") (pintype "power_in"))
      (node (ref "FL3") (pin "4") (pinfunction "GND_4") (pintype "power_in"))
      (node (ref "FL4") (pin "2") (pinfunction "GND_2") (pintype "power_in"))
      (node (ref "FL4") (pin "4") (pinfunction "GND_4") (pintype "power_in"))
      (node (ref "IC3") (pin "1") (pinfunction "NC_1") (pintype "passive"))
      (node (ref "IC3") (pin "12") (pinfunction "NC_12") (pintype "passive"))
      (node (ref "IC3") (pin "14") (pinfunction "NC_14") (pintype "passive"))
      (node (ref "IC3") (pin "16") (pinfunction "NC_16") (pintype "passive"))
      (node (ref "IC3") (pin "17") (pinfunction "NC_17") (pintype "passive"))
      (node (ref "IC3") (pin "18") (pinfunction "NC_18") (pintype "passive"))
      (node (ref "IC3") (pin "23") (pinfunction "NC_23") (pintype "passive"))
      (node (ref "IC3") (pin "25") (pinfunction "GND_25") (pintype "power_in"))
      (node (ref "IC3") (pin "3") (pinfunction "NC_3") (pintype "passive"))
      (node (ref "IC3") (pin "5") (pinfunction "NC_5") (pintype "passive"))
      (node (ref "IC4") (pin "1") (pinfunction "GND_1") (pintype "power_in"))
      (node (ref "IC4") (pin "3") (pinfunction "GND_3") (pintype "power_in"))
      (node (ref "IC4") (pin "4") (pinfunction "GND_4") (pintype "power_in"))
      (node (ref "IC4") (pin "6") (pinfunction "GND_6") (pintype "power_in"))
      (node (ref "IC4") (pin "7") (pinfunction "EP_7") (pintype "power_in"))
      (node (ref "IC5") (pin "2") (pinfunction "GND_2") (pintype "power_in"))
      (node (ref "IC5") (pin "4") (pinfunction "GND_4") (pintype "power_in"))
      (node (ref "IC7") (pin "0") (pinfunction "GND_0") (pintype "power_in"))
      (node (ref "IC7") (pin "10") (pinfunction "GND_10") (pintype "power_in"))
      (node (ref "IC7") (pin "11") (pinfunction "GND_11") (pintype "power_in"))
      (node (ref "R18") (pin "1") (pinfunction "1_1") (pintype "passive"))
      (node (ref "R19") (pin "1") (pinfunction "1_1") (pintype "passive"))
      (node (ref "R20") (pin "1") (pinfunction "1_1") (pintype "passive"))
      (node (ref "R23") (pin "1") (pinfunction "1_1") (pintype "passive"))
      (node (ref "R25") (pin "2") (pinfunction "2_2") (pintype "passive"))
      (node (ref "R27") (pin "1") (pinfunction "1_1") (pintype "passive"))
      (node (ref "R3") (pin "1") (pinfunction "1_1") (pintype "passive"))
      (node (ref "R31") (pin "1") (pinfunction "1_1") (pintype "passive"))
      (node (ref "R32") (pin "1") (pinfunction "1_1") (pintype "passive"))
      (node (ref "R4") (pin "1") (pinfunction "1_1") (pintype "passive"))
      (node (ref "R43") (pin "1") (pinfunction "1_1") (pintype "passive"))
      (node (ref "R44") (pin "1") (pinfunction "1_1") (pintype "passive"))
      (node (ref "R45") (pin "1") (pinfunction "1_1") (pintype "passive"))
      (node (ref "R46") (pin "1") (pinfunction "1_1") (pintype "passive"))
      (node (ref "R47") (pin "1") (pinfunction "1_1") (pintype "passive"))
      (node (ref "R52") (pin "1") (pinfunction "1_1") (pintype "passive"))
      (node (ref "R53") (pin "1") (pinfunction "1_1") (pintype "passive"))
      (node (ref "R54") (pin "1") (pinfunction "1_1") (pintype "passive"))
      (node (ref "R55") (pin "1") (pinfunction "1_1") (pintype "passive"))
      (node (ref "R56") (pin "1") (pinfunction "1_1") (pintype "passive"))
      (node (ref "R57") (pin "2") (pinfunction "2_2") (pintype "passive"))
      (node (ref "R58") (pin "2") (pinfunction "2_2") (pintype "passive"))
      (node (ref "U1") (pin "17") (pinfunction "EP_17") (pintype "power_in"))
      (node (ref "U1") (pin "4") (pinfunction "COMM_4") (pintype "power_in"))
      (node (ref "U1") (pin "9") (pinfunction "COMM_9") (pintype "power_in"))
    )
    (net (code "15") (name "Net-(C49-Pad2)") (class "Default")
      (node (ref "C49") (pin "2") (pinfunction "2_2") (pintype "passive"))
      (node (ref "R2") (pin "1") (pinfunction "1_1") (pintype "passive"))
      (node (ref "R3") (pin "2") (pinfunction "2_2") (pintype "passive"))
    )
    (net (code "16") (name "Net-(C50-Pad1)") (class "Default")
      (node (ref "C50") (pin "1") (pinfunction "1_1") (pintype "passive"))
      (node (ref "R2") (pin "2") (pinfunction "2_2") (pintype "passive"))
      (node (ref "R4") (pin "2") (pinfunction "2_2") (pintype "passive"))
    )
    (net (code "17") (name "Net-(C58-Pad1)") (class "Default")
      (node (ref "C58") (pin "1") (pinfunction "1_1") (pintype "passive"))
      (node (ref "C59") (pin "2") (pinfunction "2_2") (pintype "passive"))
      (node (ref "C60") (pin "2") (pinfunction "2_2") (pintype "passive"))
      (node (ref "C61") (pin "1") (pinfunction "1_1") (pintype "passive"))
      (node (ref "C62") (pin "1") (pinfunction "1_1") (pintype "passive"))
      (node (ref "L8") (pin "1") (pinfunction "1_1") (pintype "passive"))
      (node (ref "U1") (pin "10") (pinfunction "VPOS_10") (pintype "power_in"))
      (node (ref "U1") (pin "3") (pinfunction "VPOS_3") (pintype "power_in"))
    )
    (net (code "18") (name "Net-(FL2-RFIN)") (class "Default")
      (node (ref "FL2") (pin "1") (pinfunction "RFIN_1") (pintype "input"))
      (node (ref "R59") (pin "2") (pinfunction "2_2") (pintype "passive"))
    )
    (net (code "19") (name "Net-(FL2-RFOUT)") (class "Default")
      (node (ref "FL2") (pin "3") (pinfunction "RFOUT_3") (pintype "output"))
      (node (ref "FL3") (pin "1") (pinfunction "RFIN_1") (pintype "input"))
    )
    (net (code "20") (name "Net-(FL3-RFOUT)") (class "Default")
      (node (ref "FL3") (pin "3") (pinfunction "RFOUT_3") (pintype "output"))
      (node (ref "FL4") (pin "1") (pinfunction "RFIN_1") (pintype "input"))
    )
    (net (code "21") (name "Net-(FL4-RFOUT)") (class "Default")
      (node (ref "C28") (pin "1") (pinfunction "1_1") (pintype "passive"))
      (node (ref "FL4") (pin "3") (pinfunction "RFOUT_3") (pintype "output"))
    )
    (net (code "22") (name "Net-(IC3-ACG1)") (class "Default")
      (node (ref "C14") (pin "2") (pinfunction "2_2") (pintype "passive"))
      (node (ref "IC3") (pin "6") (pinfunction "ACG1_6") (pintype "passive"))
    )
    (net (code "23") (name "Net-(IC3-ACG2)") (class "Default")
      (node (ref "C15") (pin "2") (pinfunction "2_2") (pintype "passive"))
      (node (ref "IC3") (pin "7") (pinfunction "ACG2_7") (pintype "passive"))
    )
    (net (code "24") (name "Net-(IC3-ACG3)") (class "Default")
      (node (ref "C16") (pin "2") (pinfunction "2_2") (pintype "passive"))
      (node (ref "IC3") (pin "8") (pinfunction "ACG3_8") (pintype "passive"))
    )
    (net (code "25") (name "Net-(IC3-ACG4)") (class "Default")
      (node (ref "C17") (pin "2") (pinfunction "2_2") (pintype "passive"))
      (node (ref "IC3") (pin "9") (pinfunction "ACG4_9") (pintype "passive"))
    )
    (net (code "26") (name "Net-(IC3-ACG5)") (class "Default")
      (node (ref "C18") (pin "2") (pinfunction "2_2") (pintype "passive"))
      (node (ref "IC3") (pin "10") (pinfunction "ACG5_10") (pintype "passive"))
    )
    (net (code "27") (name "Net-(IC3-ACG6)") (class "Default")
      (node (ref "C19") (pin "2") (pinfunction "2_2") (pintype "passive"))
      (node (ref "IC3") (pin "11") (pinfunction "ACG6_11") (pintype "passive"))
    )
    (net (code "28") (name "Net-(IC3-ACG7)") (class "Default")
      (node (ref "C20") (pin "2") (pinfunction "2_2") (pintype "passive"))
      (node (ref "IC3") (pin "13") (pinfunction "ACG7_13") (pintype "passive"))
    )
    (net (code "29") (name "Net-(IC3-RF1)") (class "Default")
      (node (ref "C29") (pin "2") (pinfunction "2_2") (pintype "passive"))
      (node (ref "IC3") (pin "4") (pinfunction "RF1_4") (pintype "bidirectional"))
    )
    (net (code "30") (name "Net-(IC3-RF2)") (class "Default")
      (node (ref "C36") (pin "1") (pinfunction "1_1") (pintype "passive"))
      (node (ref "IC3") (pin "15") (pinfunction "RF2_15") (pintype "bidirectional"))
    )
    (net (code "31") (name "Net-(IC3-VCC)") (class "Default")
      (node (ref "C21") (pin "2") (pinfunction "2_2") (pintype "passive"))
      (node (ref "C22") (pin "2") (pinfunction "2_2") (pintype "passive"))
      (node (ref "C23") (pin "2") (pinfunction "2_2") (pintype "passive"))
      (node (ref "C24") (pin "2") (pinfunction "2_2") (pintype "passive"))
      (node (ref "IC3") (pin "2") (pinfunction "VCC_2") (pintype "power_in"))
      (node (ref "L7") (pin "2") (pinfunction "2_2") (pintype "passive"))
    )
    (net (code "32") (name "Net-(IC4-RFOUT)") (class "Default")
      (node (ref "C56") (pin "1") (pinfunction "1_1") (pintype "passive"))
      (node (ref "IC4") (pin "5") (pinfunction "RFOUT_5") (pintype "output"))
    )
    (net (code "33") (name "Net-(IC5-RF_IN)") (class "Default")
      (node (ref "C28") (pin "2") (pinfunction "2_2") (pintype "passive"))
      (node (ref "IC5") (pin "1") (pinfunction "RF_IN_1") (pintype "input"))
    )
    (net (code "34") (name "Net-(IC5-RF_OUT)") (class "Default")
      (node (ref "C29") (pin "1") (pinfunction "1_1") (pintype "passive"))
      (node (ref "IC5") (pin "3") (pinfunction "RF_OUT_3") (pintype "output"))
      (node (ref "L1") (pin "3") (pinfunction "3_3") (pintype "passive"))
    )
    (net (code "35") (name "Net-(IC7-EN)") (class "Default")
      (node (ref "IC7") (pin "5") (pinfunction "EN_5") (pintype "input"))
      (node (ref "R23") (pin "2") (pinfunction "2_2") (pintype "passive"))
    )
    (net (code "36") (name "Net-(IC7-RF1)") (class "Default")
      (node (ref "C49") (pin "1") (pinfunction "1_1") (pintype "passive"))
      (node (ref "IC7") (pin "9") (pinfunction "RF1_9") (pintype "passive"))
    )
    (net (code "37") (name "Net-(IC7-RF2)") (class "Default")
      (node (ref "C47") (pin "1") (pinfunction "1_1") (pintype "passive"))
      (node (ref "IC7") (pin "12") (pinfunction "RF2_12") (pintype "passive"))
    )
    (net (code "38") (name "Net-(IC7-RFC)") (class "Default")
      (node (ref "C36") (pin "2") (pinfunction "2_2") (pintype "passive"))
      (node (ref "IC7") (pin "3") (pinfunction "RFC_3") (pintype "passive"))
    )
    (net (code "39") (name "Net-(IC7-VDD)") (class "Default")
      (node (ref "C38") (pin "1") (pinfunction "1_1") (pintype "passive"))
      (node (ref "C39") (pin "2") (pinfunction "2_2") (pintype "passive"))
      (node (ref "C40") (pin "2") (pinfunction "2_2") (pintype "passive"))
      (node (ref "IC7") (pin "1") (pinfunction "VDD_1") (pintype "power_in"))
      (node (ref "L6") (pin "1") (pinfunction "1_1") (pintype "passive"))
    )
    (net (code "40") (name "Net-(L1-Pad1)") (class "Default")
      (node (ref "L1") (pin "1") (pinfunction "1_1") (pintype "passive"))
      (node (ref "R5") (pin "2") (pinfunction "2_2") (pintype "passive"))
    )
    (net (code "41") (name "Net-(R43-Pad2)") (class "Default")
      (node (ref "R43") (pin "2") (pinfunction "2_2") (pintype "passive"))
      (node (ref "R48") (pin "1") (pinfunction "1_1") (pintype "passive"))
      (node (ref "R52") (pin "2") (pinfunction "2_2") (pintype "passive"))
      (node (ref "R57") (pin "1") (pinfunction "1_1") (pintype "passive"))
    )
    (net (code "42") (name "Net-(R44-Pad2)") (class "Default")
      (node (ref "R44") (pin "2") (pinfunction "2_2") (pintype "passive"))
      (node (ref "R48") (pin "2") (pinfunction "2_2") (pintype "passive"))
      (node (ref "R49") (pin "1") (pinfunction "1_1") (pintype "passive"))
      (node (ref "R53") (pin "2") (pinfunction "2_2") (pintype "passive"))
    )
    (net (code "43") (name "Net-(R45-Pad2)") (class "Default")
      (node (ref "R45") (pin "2") (pinfunction "2_2") (pintype "passive"))
      (node (ref "R49") (pin "2") (pinfunction "2_2") (pintype "passive"))
      (node (ref "R50") (pin "1") (pinfunction "1_1") (pintype "passive"))
      (node (ref "R54") (pin "2") (pinfunction "2_2") (pintype "passive"))
    )
    (net (code "44") (name "Net-(R46-Pad2)") (class "Default")
      (node (ref "R46") (pin "2") (pinfunction "2_2") (pintype "passive"))
      (node (ref "R50") (pin "2") (pinfunction "2_2") (pintype "passive"))
      (node (ref "R51") (pin "2") (pinfunction "2_2") (pintype "passive"))
      (node (ref "R55") (pin "2") (pinfunction "2_2") (pintype "passive"))
    )
    (net (code "45") (name "Net-(R47-Pad2)") (class "Default")
      (node (ref "R47") (pin "2") (pinfunction "2_2") (pintype "passive"))
      (node (ref "R51") (pin "1") (pinfunction "1_1") (pintype "passive"))
      (node (ref "R56") (pin "2") (pinfunction "2_2") (pintype "passive"))
      (node (ref "R58") (pin "1") (pinfunction "1_1") (pintype "passive"))
    )
    (net (code "46") (name "Net-(U1-CHPF)") (class "Default")
      (node (ref "C58") (pin "2") (pinfunction "2_2") (pintype "passive"))
      (node (ref "U1") (pin "2") (pinfunction "CHPF_2") (pintype "passive"))
    )
    (net (code "47") (name "Net-(U1-CLPF)") (class "Default")
      (node (ref "C57") (pin "1") (pinfunction "1_1") (pintype "passive"))
      (node (ref "U1") (pin "5") (pinfunction "CLPF_5") (pintype "passive"))
    )
    (net (code "48") (name "Net-(U1-INHI)") (class "Default")
      (node (ref "C56") (pin "2") (pinfunction "2_2") (pintype "passive"))
      (node (ref "U1") (pin "14") (pinfunction "INHI_14") (pintype "input"))
    )
    (net (code "49") (name "Net-(U1-INLO)") (class "Default")
      (node (ref "C55") (pin "2") (pinfunction "2_2") (pintype "passive"))
      (node (ref "U1") (pin "15") (pinfunction "INLO_15") (pintype "input"))
    )
    (net (code "50") (name "Net-(U1-TCM1)") (class "Default")
      (node (ref "R29") (pin "1") (pinfunction "1_1") (pintype "passive"))
      (node (ref "R31") (pin "2") (pinfunction "2_2") (pintype "passive"))
      (node (ref "U1") (pin "16") (pinfunction "TCM1_16") (pintype "passive"))
    )
    (net (code "51") (name "Net-(U1-TCM2{slash}PWDN)") (class "Default")
      (node (ref "R30") (pin "2") (pinfunction "2_2") (pintype "passive"))
      (node (ref "R32") (pin "2") (pinfunction "2_2") (pintype "passive"))
      (node (ref "U1") (pin "1") (pinfunction "TCM2/PWDN_1") (pintype "input"))
    )
    (net (code "52") (name "Net-(U1-VOUT)") (class "Default")
      (node (ref "R26") (pin "1") (pinfunction "1_1") (pintype "passive"))
      (node (ref "U1") (pin "6") (pinfunction "VOUT_6") (pintype "output"))
      (node (ref "U1") (pin "7") (pinfunction "VSET_7") (pintype "input"))
    )
    (net (code "53") (name "Net-(U1-VTGT)") (class "Default")
      (node (ref "R25") (pin "1") (pinfunction "1_1") (pintype "passive"))
      (node (ref "R28") (pin "2") (pinfunction "2_2") (pintype "passive"))
      (node (ref "U1") (pin "12") (pinfunction "VTGT_12") (pintype "input"))
    )
    (net (code "54") (name "VCCP_5V0") (class "Default")
      (node (ref "L6") (pin "2") (pinfunction "2_2") (pintype "passive"))
      (node (ref "L7") (pin "1") (pinfunction "1_1") (pintype "passive"))
      (node (ref "L8") (pin "2") (pinfunction "2_2") (pintype "passive"))
    )
    (net (code "55") (name "VCCP_11V5_A") (class "Default")
      (node (ref "C12") (pin "2") (pinfunction "2_2") (pintype "passive"))
      (node (ref "C13") (pin "2") (pinfunction "2_2") (pintype "passive"))
      (node (ref "R5") (pin "1") (pinfunction "1_1") (pintype "passive"))
    )
    (net (code "56") (name "unconnected-(IC3-SERIAL_OUTPUT-Pad19)") (class "Default")
      (node (ref "IC3") (pin "19") (pinfunction "SERIAL_OUTPUT_19") (pintype "output"))
    )
    (net (code "57") (name "unconnected-(U1-NC-Pad13)") (class "Default")
      (node (ref "U1") (pin "13") (pinfunction "NC_13") (pintype "passive"))
    )
  )
)
